# TIMER555_copy.net
KiCad netlist of a schematic drawn in EAGLE
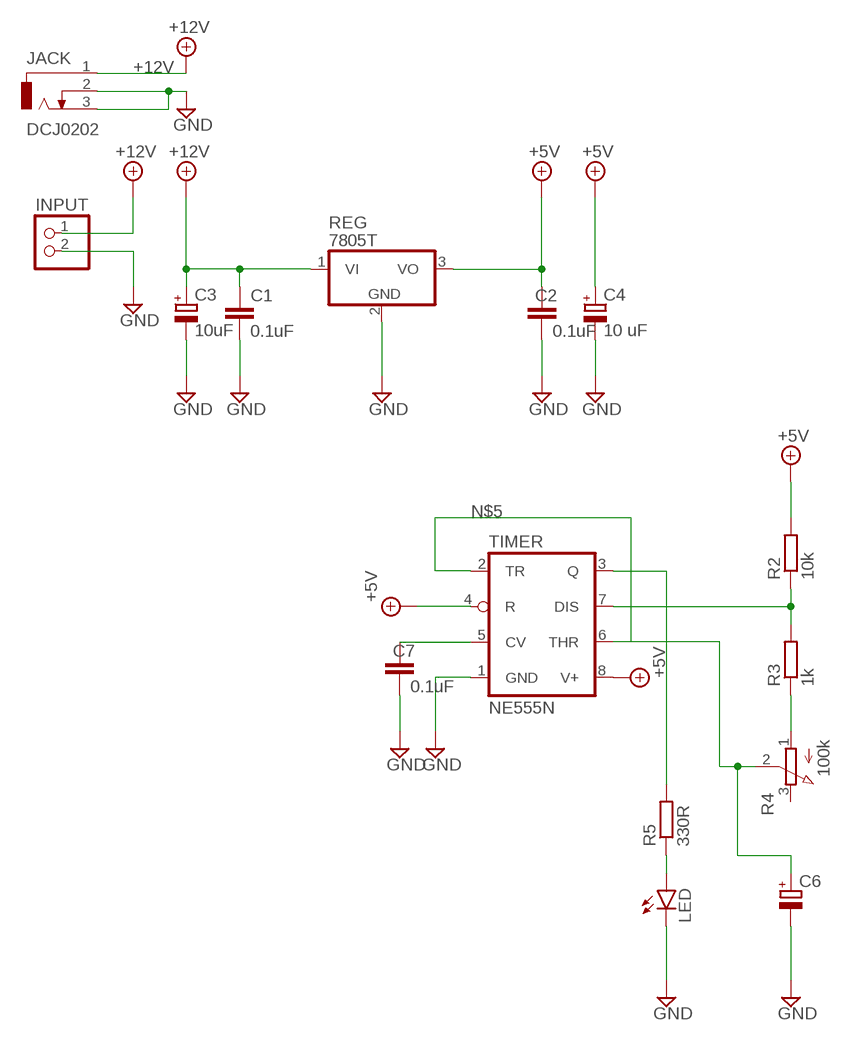
[diagram p0: schematic, sheet 1]

(export (version "E")
  (design (tool "Eeschema 10.0.6"))
  (components
    (comp (ref "C1")
      (value "0.1uF")
      (footprint "eagle-import:C050-030X075")
      (libsource (lib "eagle-import") (part "C-EU050-030X075"))
    )
    (comp (ref "C2")
      (value "0.1uF")
      (footprint "eagle-import:C050-030X075")
      (libsource (lib "eagle-import") (part "C-EU050-030X075"))
    )
    (comp (ref "C3")
      (value "10uF")
      (footprint "eagle-import:E3,5-8")
      (libsource (lib "eagle-import") (part "CPOL-EUE3.5-8"))
    )
    (comp (ref "C4")
      (value "10 uF")
      (footprint "eagle-import:E3,5-8")
      (libsource (lib "eagle-import") (part "CPOL-EUE3.5-8"))
    )
    (comp (ref "C6")
      (value "CPOL-EUE3.5-8")
      (footprint "eagle-import:E3,5-8")
      (libsource (lib "eagle-import") (part "CPOL-EUE3.5-8"))
    )
    (comp (ref "C7")
      (value "0.1uF")
      (footprint "eagle-import:C050-030X075")
      (libsource (lib "eagle-import") (part "C-EU050-030X075"))
    )
    (comp (ref "INPUT")
      (value "PINHD-1X2")
      (footprint "eagle-import:1X02")
      (libsource (lib "eagle-import") (part "PINHD-1X2"))
    )
    (comp (ref "JACK")
      (value "DCJ0202")
      (footprint "eagle-import:DCJ0202")
      (libsource (lib "eagle-import") (part "DCJ0202"))
    )
    (comp (ref "LED")
      (value "LED5MM")
      (footprint "eagle-import:LED5MM")
      (libsource (lib "eagle-import") (part "LED5MM"))
    )
    (comp (ref "R2")
      (value "10k")
      (footprint "eagle-import:0207_10")
      (libsource (lib "eagle-import") (part "R-EU_0207/10"))
    )
    (comp (ref "R3")
      (value "1k")
      (footprint "eagle-import:0207_10")
      (libsource (lib "eagle-import") (part "R-EU_0207/10"))
    )
    (comp (ref "R4")
      (value "100k")
      (footprint "eagle-import:3RP_1610N")
      (libsource (lib "eagle-import") (part "3RP/1610N"))
    )
    (comp (ref "R5")
      (value "330R")
      (footprint "eagle-import:0207_10")
      (libsource (lib "eagle-import") (part "R-EU_0207/10"))
    )
    (comp (ref "REG")
      (value "7805T")
      (footprint "eagle-import:TO220H")
      (libsource (lib "eagle-import") (part "78T05"))
    )
    (comp (ref "TIMER")
      (value "NE555N")
      (footprint "eagle-import:DIL08")
      (libsource (lib "eagle-import") (part "555NNE"))
    )
  )
  (nets
    (net (code "1") (name "+5V") (class "Default")
      (node (ref "C2") (pin "1") (pinfunction "1_1") (pintype "passive"))
      (node (ref "C4") (pin "+") (pinfunction "+_+") (pintype "passive"))
      (node (ref "R2") (pin "2") (pinfunction "2_2") (pintype "passive"))
      (node (ref "REG") (pin "3") (pinfunction "VO_3") (pintype "passive"))
      (node (ref "TIMER") (pin "4") (pinfunction "R_4") (pintype "input"))
      (node (ref "TIMER") (pin "8") (pinfunction "V+_8") (pintype "power_in"))
    )
    (net (code "2") (name "+12V") (class "Default")
      (node (ref "C1") (pin "1") (pinfunction "1_1") (pintype "passive"))
      (node (ref "C3") (pin "+") (pinfunction "+_+") (pintype "passive"))
      (node (ref "INPUT") (pin "1") (pinfunction "1_1") (pintype "passive"))
      (node (ref "JACK") (pin "1") (pinfunction "1_1") (pintype "passive"))
      (node (ref "REG") (pin "1") (pinfunction "VI_1") (pintype "input"))
    )
    (net (code "3") (name "/N$5") (class "Default")
      (node (ref "C6") (pin "+") (pinfunction "+_+") (pintype "passive"))
      (node (ref "R4") (pin "2") (pinfunction "S_2") (pintype "passive"))
      (node (ref "TIMER") (pin "2") (pinfunction "TR_2") (pintype "input"))
      (node (ref "TIMER") (pin "6") (pinfunction "THR_6") (pintype "input"))
    )
    (net (code "4") (name "GND") (class "Default")
      (node (ref "C1") (pin "2") (pinfunction "2_2") (pintype "passive"))
      (node (ref "C2") (pin "2") (pinfunction "2_2") (pintype "passive"))
      (node (ref "C3") (pin "-") (pinfunction "-_-") (pintype "passive"))
      (node (ref "C4") (pin "-") (pinfunction "-_-") (pintype "passive"))
      (node (ref "C6") (pin "-") (pinfunction "-_-") (pintype "passive"))
      (node (ref "C7") (pin "2") (pinfunction "2_2") (pintype "passive"))
      (node (ref "INPUT") (pin "2") (pinfunction "2_2") (pintype "passive"))
      (node (ref "JACK") (pin "2") (pinfunction "2_2") (pintype "passive"))
      (node (ref "JACK") (pin "3") (pinfunction "3_3") (pintype "passive"))
      (node (ref "LED") (pin "K") (pinfunction "C_K") (pintype "passive"))
      (node (ref "REG") (pin "2") (pinfunction "GND_2") (pintype "passive"))
      (node (ref "TIMER") (pin "1") (pinfunction "GND_1") (pintype "power_in"))
    )
    (net (code "5") (name "Net-(LED-PadA)") (class "Default")
      (node (ref "LED") (pin "A") (pinfunction "A_A") (pintype "passive"))
      (node (ref "R5") (pin "1") (pinfunction "1_1") (pintype "passive"))
    )
    (net (code "6") (name "Net-(R4-A)") (class "Default")
      (node (ref "R3") (pin "1") (pinfunction "1_1") (pintype "passive"))
      (node (ref "R4") (pin "1") (pinfunction "A_1") (pintype "passive"))
    )
    (net (code "7") (name "Net-(TIMER-CV)") (class "Default")
      (node (ref "C7") (pin "1") (pinfunction "1_1") (pintype "passive"))
      (node (ref "TIMER") (pin "5") (pinfunction "CV_5") (pintype "input"))
    )
    (net (code "8") (name "Net-(TIMER-DIS)") (class "Default")
      (node (ref "R2") (pin "1") (pinfunction "1_1") (pintype "passive"))
      (node (ref "R3") (pin "2") (pinfunction "2_2") (pintype "passive"))
      (node (ref "TIMER") (pin "7") (pinfunction "DIS_7") (pintype "input"))
    )
    (net (code "9") (name "Net-(TIMER-Q)") (class "Default")
      (node (ref "R5") (pin "2") (pinfunction "2_2") (pintype "passive"))
      (node (ref "TIMER") (pin "3") (pinfunction "Q_3") (pintype "output"))
    )
    (net (code "10") (name "unconnected-(R4-E-Pad3)") (class "Default")
      (node (ref "R4") (pin "3") (pinfunction "E_3") (pintype "passive"))
    )
  )
)
